# DASH_V_3_POTS.net
KiCad netlist of a schematic drawn in Altium Designer
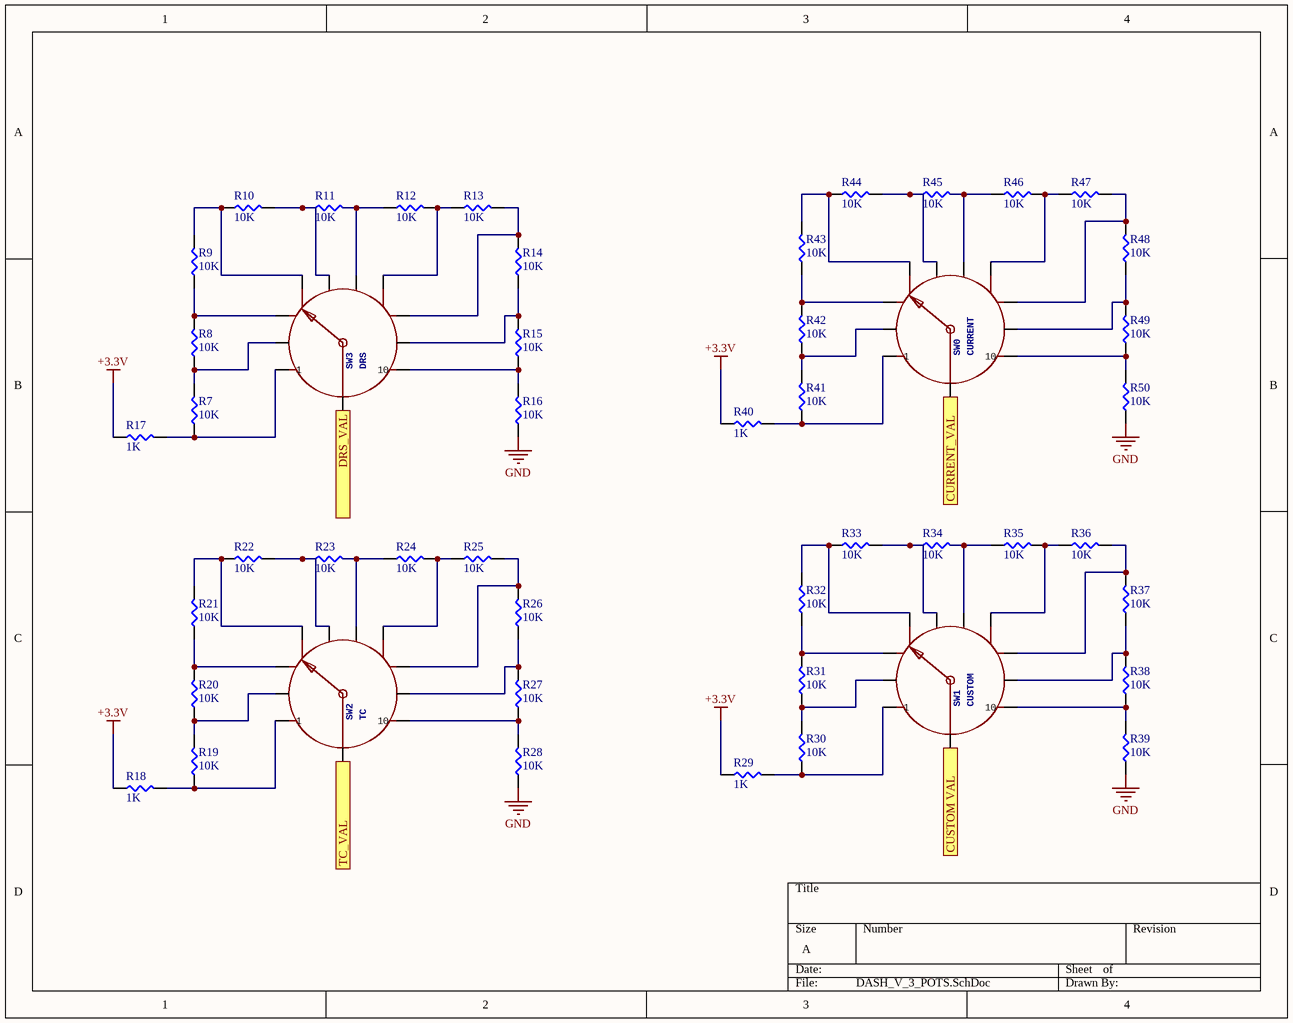
[diagram p0: DASH_V_3_POTS.SchDoc]

(export (version "E")
  (design (tool "Eeschema 10.0.6"))
  (components
    (comp (ref "R7")
      (value "10K")
      (footprint "RES-0603")
      (libsource (lib "ife19_Elec_Library") (part "RES-0603"))
    )
    (comp (ref "R8")
      (value "10K")
      (footprint "RES-0603")
      (libsource (lib "ife19_Elec_Library") (part "RES-0603"))
    )
    (comp (ref "R9")
      (value "10K")
      (footprint "RES-0603")
      (libsource (lib "ife19_Elec_Library") (part "RES-0603"))
    )
    (comp (ref "R10")
      (value "10K")
      (footprint "RES-0603")
      (libsource (lib "ife19_Elec_Library") (part "RES-0603"))
    )
    (comp (ref "R11")
      (value "10K")
      (footprint "RES-0603")
      (libsource (lib "ife19_Elec_Library") (part "RES-0603"))
    )
    (comp (ref "R12")
      (value "10K")
      (footprint "RES-0603")
      (libsource (lib "ife19_Elec_Library") (part "RES-0603"))
    )
    (comp (ref "R13")
      (value "10K")
      (footprint "RES-0603")
      (libsource (lib "ife19_Elec_Library") (part "RES-0603"))
    )
    (comp (ref "R14")
      (value "10K")
      (footprint "RES-0603")
      (libsource (lib "ife19_Elec_Library") (part "RES-0603"))
    )
    (comp (ref "R15")
      (value "10K")
      (footprint "RES-0603")
      (libsource (lib "ife19_Elec_Library") (part "RES-0603"))
    )
    (comp (ref "R16")
      (value "10K")
      (footprint "RES-0603")
      (libsource (lib "ife19_Elec_Library") (part "RES-0603"))
    )
    (comp (ref "R17")
      (value "1K")
      (footprint "RES-0603")
      (libsource (lib "ife19_Elec_Library") (part "RES-0603"))
    )
    (comp (ref "R18")
      (value "1K")
      (footprint "RES-0603")
      (libsource (lib "ife19_Elec_Library") (part "RES-0603"))
    )
    (comp (ref "R19")
      (value "10K")
      (footprint "RES-0603")
      (libsource (lib "ife19_Elec_Library") (part "RES-0603"))
    )
    (comp (ref "R20")
      (value "10K")
      (footprint "RES-0603")
      (libsource (lib "ife19_Elec_Library") (part "RES-0603"))
    )
    (comp (ref "R21")
      (value "10K")
      (footprint "RES-0603")
      (libsource (lib "ife19_Elec_Library") (part "RES-0603"))
    )
    (comp (ref "R22")
      (value "10K")
      (footprint "RES-0603")
      (libsource (lib "ife19_Elec_Library") (part "RES-0603"))
    )
    (comp (ref "R23")
      (value "10K")
      (footprint "RES-0603")
      (libsource (lib "ife19_Elec_Library") (part "RES-0603"))
    )
    (comp (ref "R24")
      (value "10K")
      (footprint "RES-0603")
      (libsource (lib "ife19_Elec_Library") (part "RES-0603"))
    )
    (comp (ref "R25")
      (value "10K")
      (footprint "RES-0603")
      (libsource (lib "ife19_Elec_Library") (part "RES-0603"))
    )
    (comp (ref "R26")
      (value "10K")
      (footprint "RES-0603")
      (libsource (lib "ife19_Elec_Library") (part "RES-0603"))
    )
    (comp (ref "R27")
      (value "10K")
      (footprint "RES-0603")
      (libsource (lib "ife19_Elec_Library") (part "RES-0603"))
    )
    (comp (ref "R28")
      (value "10K")
      (footprint "RES-0603")
      (libsource (lib "ife19_Elec_Library") (part "RES-0603"))
    )
    (comp (ref "R29")
      (value "1K")
      (footprint "RES-0603")
      (libsource (lib "ife19_Elec_Library") (part "RES-0603"))
    )
    (comp (ref "R30")
      (value "10K")
      (footprint "RES-0603")
      (libsource (lib "ife19_Elec_Library") (part "RES-0603"))
    )
    (comp (ref "R31")
      (value "10K")
      (footprint "RES-0603")
      (libsource (lib "ife19_Elec_Library") (part "RES-0603"))
    )
    (comp (ref "R32")
      (value "10K")
      (footprint "RES-0603")
      (libsource (lib "ife19_Elec_Library") (part "RES-0603"))
    )
    (comp (ref "R33")
      (value "10K")
      (footprint "RES-0603")
      (libsource (lib "ife19_Elec_Library") (part "RES-0603"))
    )
    (comp (ref "R34")
      (value "10K")
      (footprint "RES-0603")
      (libsource (lib "ife19_Elec_Library") (part "RES-0603"))
    )
    (comp (ref "R35")
      (value "10K")
      (footprint "RES-0603")
      (libsource (lib "ife19_Elec_Library") (part "RES-0603"))
    )
    (comp (ref "R36")
      (value "10K")
      (footprint "RES-0603")
      (libsource (lib "ife19_Elec_Library") (part "RES-0603"))
    )
    (comp (ref "R37")
      (value "10K")
      (footprint "RES-0603")
      (libsource (lib "ife19_Elec_Library") (part "RES-0603"))
    )
    (comp (ref "R38")
      (value "10K")
      (footprint "RES-0603")
      (libsource (lib "ife19_Elec_Library") (part "RES-0603"))
    )
    (comp (ref "R39")
      (value "10K")
      (footprint "RES-0603")
      (libsource (lib "ife19_Elec_Library") (part "RES-0603"))
    )
    (comp (ref "R40")
      (value "1K")
      (footprint "RES-0603")
      (libsource (lib "ife19_Elec_Library") (part "RES-0603"))
    )
    (comp (ref "R41")
      (value "10K")
      (footprint "RES-0603")
      (libsource (lib "ife19_Elec_Library") (part "RES-0603"))
    )
    (comp (ref "R42")
      (value "10K")
      (footprint "RES-0603")
      (libsource (lib "ife19_Elec_Library") (part "RES-0603"))
    )
    (comp (ref "R43")
      (value "10K")
      (footprint "RES-0603")
      (libsource (lib "ife19_Elec_Library") (part "RES-0603"))
    )
    (comp (ref "R44")
      (value "10K")
      (footprint "RES-0603")
      (libsource (lib "ife19_Elec_Library") (part "RES-0603"))
    )
    (comp (ref "R45")
      (value "10K")
      (footprint "RES-0603")
      (libsource (lib "ife19_Elec_Library") (part "RES-0603"))
    )
    (comp (ref "R46")
      (value "10K")
      (footprint "RES-0603")
      (libsource (lib "ife19_Elec_Library") (part "RES-0603"))
    )
    (comp (ref "R47")
      (value "10K")
      (footprint "RES-0603")
      (libsource (lib "ife19_Elec_Library") (part "RES-0603"))
    )
    (comp (ref "R48")
      (value "10K")
      (footprint "RES-0603")
      (libsource (lib "ife19_Elec_Library") (part "RES-0603"))
    )
    (comp (ref "R49")
      (value "10K")
      (footprint "RES-0603")
      (libsource (lib "ife19_Elec_Library") (part "RES-0603"))
    )
    (comp (ref "R50")
      (value "10K")
      (footprint "RES-0603")
      (libsource (lib "ife19_Elec_Library") (part "RES-0603"))
    )
    (comp (ref "SW0")
      (value "CURRENT")
      (footprint "SPARKFUN-ELECTROMECHANICAL_ROTARY_SWITCH_1X10_KIT")
      (libsource (lib "Rotary_Switch_Potentiometer_v10") (part "SPARKFUN-ELECTROMECHANICAL_SWITCH_ROTARY_1X10KIT"))
    )
    (comp (ref "SW1")
      (value "CUSTOM")
      (footprint "SPARKFUN-ELECTROMECHANICAL_ROTARY_SWITCH_1X10_KIT")
      (libsource (lib "Rotary_Switch_Potentiometer_v10") (part "SPARKFUN-ELECTROMECHANICAL_SWITCH_ROTARY_1X10KIT"))
    )
    (comp (ref "SW2")
      (value "TC")
      (footprint "SPARKFUN-ELECTROMECHANICAL_ROTARY_SWITCH_1X10_KIT")
      (libsource (lib "Rotary_Switch_Potentiometer_v10") (part "SPARKFUN-ELECTROMECHANICAL_SWITCH_ROTARY_1X10KIT"))
    )
    (comp (ref "SW3")
      (value "DRS")
      (footprint "SPARKFUN-ELECTROMECHANICAL_ROTARY_SWITCH_1X10_KIT")
      (libsource (lib "Rotary_Switch_Potentiometer_v10") (part "SPARKFUN-ELECTROMECHANICAL_SWITCH_ROTARY_1X10KIT"))
    )
  )
  (nets
    (net (code "1") (name "+3.3V") (class "Default")
      (node (ref "R17") (pin "1") (pinfunction "1_1") (pintype "passive"))
      (node (ref "R18") (pin "1") (pinfunction "1_1") (pintype "passive"))
      (node (ref "R29") (pin "1") (pinfunction "1_1") (pintype "passive"))
      (node (ref "R40") (pin "1") (pinfunction "1_1") (pintype "passive"))
    )
    (net (code "2") (name "/CURRENT_VAL") (class "Default")
      (node (ref "SW0") (pin "COMMON") (pinfunction "COMMON_COMMON") (pintype "passive"))
    )
    (net (code "3") (name "/CUSTOM VAL") (class "Default")
      (node (ref "SW1") (pin "COMMON") (pinfunction "COMMON_COMMON") (pintype "passive"))
    )
    (net (code "4") (name "/DRS_VAL") (class "Default")
      (node (ref "SW3") (pin "COMMON") (pinfunction "COMMON_COMMON") (pintype "passive"))
    )
    (net (code "5") (name "/TC_VAL") (class "Default")
      (node (ref "SW2") (pin "COMMON") (pinfunction "COMMON_COMMON") (pintype "passive"))
    )
    (net (code "6") (name "GND") (class "Default")
      (node (ref "R16") (pin "1") (pinfunction "1_1") (pintype "passive"))
      (node (ref "R28") (pin "1") (pinfunction "1_1") (pintype "passive"))
      (node (ref "R39") (pin "1") (pinfunction "1_1") (pintype "passive"))
      (node (ref "R50") (pin "1") (pinfunction "1_1") (pintype "passive"))
    )
    (net (code "7") (name "Net-(R7-Pad2)") (class "Default")
      (node (ref "R7") (pin "2") (pinfunction "2_2") (pintype "passive"))
      (node (ref "R8") (pin "1") (pinfunction "1_1") (pintype "passive"))
      (node (ref "SW3") (pin "2") (pinfunction "2_2") (pintype "passive"))
    )
    (net (code "8") (name "Net-(R8-Pad2)") (class "Default")
      (node (ref "R8") (pin "2") (pinfunction "2_2") (pintype "passive"))
      (node (ref "R9") (pin "1") (pinfunction "1_1") (pintype "passive"))
      (node (ref "SW3") (pin "3") (pinfunction "3_3") (pintype "passive"))
    )
    (net (code "9") (name "Net-(R10-Pad1)") (class "Default")
      (node (ref "R10") (pin "1") (pinfunction "1_1") (pintype "passive"))
      (node (ref "R9") (pin "2") (pinfunction "2_2") (pintype "passive"))
      (node (ref "SW3") (pin "4") (pinfunction "4_4") (pintype "passive"))
    )
    (net (code "10") (name "Net-(R10-Pad2)") (class "Default")
      (node (ref "R10") (pin "2") (pinfunction "2_2") (pintype "passive"))
      (node (ref "R11") (pin "1") (pinfunction "1_1") (pintype "passive"))
      (node (ref "SW3") (pin "5") (pinfunction "5_5") (pintype "passive"))
    )
    (net (code "11") (name "Net-(R11-Pad2)") (class "Default")
      (node (ref "R11") (pin "2") (pinfunction "2_2") (pintype "passive"))
      (node (ref "R12") (pin "1") (pinfunction "1_1") (pintype "passive"))
      (node (ref "SW3") (pin "6") (pinfunction "6_6") (pintype "passive"))
    )
    (net (code "12") (name "Net-(R12-Pad2)") (class "Default")
      (node (ref "R12") (pin "2") (pinfunction "2_2") (pintype "passive"))
      (node (ref "R13") (pin "1") (pinfunction "1_1") (pintype "passive"))
      (node (ref "SW3") (pin "7") (pinfunction "7_7") (pintype "passive"))
    )
    (net (code "13") (name "Net-(R13-Pad2)") (class "Default")
      (node (ref "R13") (pin "2") (pinfunction "2_2") (pintype "passive"))
      (node (ref "R14") (pin "2") (pinfunction "2_2") (pintype "passive"))
      (node (ref "SW3") (pin "8") (pinfunction "8_8") (pintype "passive"))
    )
    (net (code "14") (name "Net-(R14-Pad1)") (class "Default")
      (node (ref "R14") (pin "1") (pinfunction "1_1") (pintype "passive"))
      (node (ref "R15") (pin "2") (pinfunction "2_2") (pintype "passive"))
      (node (ref "SW3") (pin "9") (pinfunction "9_9") (pintype "passive"))
    )
    (net (code "15") (name "Net-(R15-Pad1)") (class "Default")
      (node (ref "R15") (pin "1") (pinfunction "1_1") (pintype "passive"))
      (node (ref "R16") (pin "2") (pinfunction "2_2") (pintype "passive"))
      (node (ref "SW3") (pin "10") (pinfunction "10_10") (pintype "passive"))
    )
    (net (code "16") (name "Net-(R17-Pad2)") (class "Default")
      (node (ref "R17") (pin "2") (pinfunction "2_2") (pintype "passive"))
      (node (ref "R7") (pin "1") (pinfunction "1_1") (pintype "passive"))
      (node (ref "SW3") (pin "1") (pinfunction "1_1") (pintype "passive"))
    )
    (net (code "17") (name "Net-(R18-Pad2)") (class "Default")
      (node (ref "R18") (pin "2") (pinfunction "2_2") (pintype "passive"))
      (node (ref "R19") (pin "1") (pinfunction "1_1") (pintype "passive"))
      (node (ref "SW2") (pin "1") (pinfunction "1_1") (pintype "passive"))
    )
    (net (code "18") (name "Net-(R19-Pad2)") (class "Default")
      (node (ref "R19") (pin "2") (pinfunction "2_2") (pintype "passive"))
      (node (ref "R20") (pin "1") (pinfunction "1_1") (pintype "passive"))
      (node (ref "SW2") (pin "2") (pinfunction "2_2") (pintype "passive"))
    )
    (net (code "19") (name "Net-(R20-Pad2)") (class "Default")
      (node (ref "R20") (pin "2") (pinfunction "2_2") (pintype "passive"))
      (node (ref "R21") (pin "1") (pinfunction "1_1") (pintype "passive"))
      (node (ref "SW2") (pin "3") (pinfunction "3_3") (pintype "passive"))
    )
    (net (code "20") (name "Net-(R21-Pad2)") (class "Default")
      (node (ref "R21") (pin "2") (pinfunction "2_2") (pintype "passive"))
      (node (ref "R22") (pin "1") (pinfunction "1_1") (pintype "passive"))
      (node (ref "SW2") (pin "4") (pinfunction "4_4") (pintype "passive"))
    )
    (net (code "21") (name "Net-(R22-Pad2)") (class "Default")
      (node (ref "R22") (pin "2") (pinfunction "2_2") (pintype "passive"))
      (node (ref "R23") (pin "1") (pinfunction "1_1") (pintype "passive"))
      (node (ref "SW2") (pin "5") (pinfunction "5_5") (pintype "passive"))
    )
    (net (code "22") (name "Net-(R23-Pad2)") (class "Default")
      (node (ref "R23") (pin "2") (pinfunction "2_2") (pintype "passive"))
      (node (ref "R24") (pin "1") (pinfunction "1_1") (pintype "passive"))
      (node (ref "SW2") (pin "6") (pinfunction "6_6") (pintype "passive"))
    )
    (net (code "23") (name "Net-(R24-Pad2)") (class "Default")
      (node (ref "R24") (pin "2") (pinfunction "2_2") (pintype "passive"))
      (node (ref "R25") (pin "1") (pinfunction "1_1") (pintype "passive"))
      (node (ref "SW2") (pin "7") (pinfunction "7_7") (pintype "passive"))
    )
    (net (code "24") (name "Net-(R25-Pad2)") (class "Default")
      (node (ref "R25") (pin "2") (pinfunction "2_2") (pintype "passive"))
      (node (ref "R26") (pin "2") (pinfunction "2_2") (pintype "passive"))
      (node (ref "SW2") (pin "8") (pinfunction "8_8") (pintype "passive"))
    )
    (net (code "25") (name "Net-(R26-Pad1)") (class "Default")
      (node (ref "R26") (pin "1") (pinfunction "1_1") (pintype "passive"))
      (node (ref "R27") (pin "2") (pinfunction "2_2") (pintype "passive"))
      (node (ref "SW2") (pin "9") (pinfunction "9_9") (pintype "passive"))
    )
    (net (code "26") (name "Net-(R27-Pad1)") (class "Default")
      (node (ref "R27") (pin "1") (pinfunction "1_1") (pintype "passive"))
      (node (ref "R28") (pin "2") (pinfunction "2_2") (pintype "passive"))
      (node (ref "SW2") (pin "10") (pinfunction "10_10") (pintype "passive"))
    )
    (net (code "27") (name "Net-(R29-Pad2)") (class "Default")
      (node (ref "R29") (pin "2") (pinfunction "2_2") (pintype "passive"))
      (node (ref "R30") (pin "1") (pinfunction "1_1") (pintype "passive"))
      (node (ref "SW1") (pin "1") (pinfunction "1_1") (pintype "passive"))
    )
    (net (code "28") (name "Net-(R30-Pad2)") (class "Default")
      (node (ref "R30") (pin "2") (pinfunction "2_2") (pintype "passive"))
      (node (ref "R31") (pin "1") (pinfunction "1_1") (pintype "passive"))
      (node (ref "SW1") (pin "2") (pinfunction "2_2") (pintype "passive"))
    )
    (net (code "29") (name "Net-(R31-Pad2)") (class "Default")
      (node (ref "R31") (pin "2") (pinfunction "2_2") (pintype "passive"))
      (node (ref "R32") (pin "1") (pinfunction "1_1") (pintype "passive"))
      (node (ref "SW1") (pin "3") (pinfunction "3_3") (pintype "passive"))
    )
    (net (code "30") (name "Net-(R32-Pad2)") (class "Default")
      (node (ref "R32") (pin "2") (pinfunction "2_2") (pintype "passive"))
      (node (ref "R33") (pin "1") (pinfunction "1_1") (pintype "passive"))
      (node (ref "SW1") (pin "4") (pinfunction "4_4") (pintype "passive"))
    )
    (net (code "31") (name "Net-(R33-Pad2)") (class "Default")
      (node (ref "R33") (pin "2") (pinfunction "2_2") (pintype "passive"))
      (node (ref "R34") (pin "1") (pinfunction "1_1") (pintype "passive"))
      (node (ref "SW1") (pin "5") (pinfunction "5_5") (pintype "passive"))
    )
    (net (code "32") (name "Net-(R34-Pad2)") (class "Default")
      (node (ref "R34") (pin "2") (pinfunction "2_2") (pintype "passive"))
      (node (ref "R35") (pin "1") (pinfunction "1_1") (pintype "passive"))
      (node (ref "SW1") (pin "6") (pinfunction "6_6") (pintype "passive"))
    )
    (net (code "33") (name "Net-(R35-Pad2)") (class "Default")
      (node (ref "R35") (pin "2") (pinfunction "2_2") (pintype "passive"))
      (node (ref "R36") (pin "1") (pinfunction "1_1") (pintype "passive"))
      (node (ref "SW1") (pin "7") (pinfunction "7_7") (pintype "passive"))
    )
    (net (code "34") (name "Net-(R36-Pad2)") (class "Default")
      (node (ref "R36") (pin "2") (pinfunction "2_2") (pintype "passive"))
      (node (ref "R37") (pin "2") (pinfunction "2_2") (pintype "passive"))
      (node (ref "SW1") (pin "8") (pinfunction "8_8") (pintype "passive"))
    )
    (net (code "35") (name "Net-(R37-Pad1)") (class "Default")
      (node (ref "R37") (pin "1") (pinfunction "1_1") (pintype "passive"))
      (node (ref "R38") (pin "2") (pinfunction "2_2") (pintype "passive"))
      (node (ref "SW1") (pin "9") (pinfunction "9_9") (pintype "passive"))
    )
    (net (code "36") (name "Net-(R38-Pad1)") (class "Default")
      (node (ref "R38") (pin "1") (pinfunction "1_1") (pintype "passive"))
      (node (ref "R39") (pin "2") (pinfunction "2_2") (pintype "passive"))
      (node (ref "SW1") (pin "10") (pinfunction "10_10") (pintype "passive"))
    )
    (net (code "37") (name "Net-(R40-Pad2)") (class "Default")
      (node (ref "R40") (pin "2") (pinfunction "2_2") (pintype "passive"))
      (node (ref "R41") (pin "1") (pinfunction "1_1") (pintype "passive"))
      (node (ref "SW0") (pin "1") (pinfunction "1_1") (pintype "passive"))
    )
    (net (code "38") (name "Net-(R41-Pad2)") (class "Default")
      (node (ref "R41") (pin "2") (pinfunction "2_2") (pintype "passive"))
      (node (ref "R42") (pin "1") (pinfunction "1_1") (pintype "passive"))
      (node (ref "SW0") (pin "2") (pinfunction "2_2") (pintype "passive"))
    )
    (net (code "39") (name "Net-(R42-Pad2)") (class "Default")
      (node (ref "R42") (pin "2") (pinfunction "2_2") (pintype "passive"))
      (node (ref "R43") (pin "1") (pinfunction "1_1") (pintype "passive"))
      (node (ref "SW0") (pin "3") (pinfunction "3_3") (pintype "passive"))
    )
    (net (code "40") (name "Net-(R43-Pad2)") (class "Default")
      (node (ref "R43") (pin "2") (pinfunction "2_2") (pintype "passive"))
      (node (ref "R44") (pin "1") (pinfunction "1_1") (pintype "passive"))
      (node (ref "SW0") (pin "4") (pinfunction "4_4") (pintype "passive"))
    )
    (net (code "41") (name "Net-(R44-Pad2)") (class "Default")
      (node (ref "R44") (pin "2") (pinfunction "2_2") (pintype "passive"))
      (node (ref "R45") (pin "1") (pinfunction "1_1") (pintype "passive"))
      (node (ref "SW0") (pin "5") (pinfunction "5_5") (pintype "passive"))
    )
    (net (code "42") (name "Net-(R45-Pad2)") (class "Default")
      (node (ref "R45") (pin "2") (pinfunction "2_2") (pintype "passive"))
      (node (ref "R46") (pin "1") (pinfunction "1_1") (pintype "passive"))
      (node (ref "SW0") (pin "6") (pinfunction "6_6") (pintype "passive"))
    )
    (net (code "43") (name "Net-(R46-Pad2)") (class "Default")
      (node (ref "R46") (pin "2") (pinfunction "2_2") (pintype "passive"))
      (node (ref "R47") (pin "1") (pinfunction "1_1") (pintype "passive"))
      (node (ref "SW0") (pin "7") (pinfunction "7_7") (pintype "passive"))
    )
    (net (code "44") (name "Net-(R47-Pad2)") (class "Default")
      (node (ref "R47") (pin "2") (pinfunction "2_2") (pintype "passive"))
      (node (ref "R48") (pin "2") (pinfunction "2_2") (pintype "passive"))
      (node (ref "SW0") (pin "8") (pinfunction "8_8") (pintype "passive"))
    )
    (net (code "45") (name "Net-(R48-Pad1)") (class "Default")
      (node (ref "R48") (pin "1") (pinfunction "1_1") (pintype "passive"))
      (node (ref "R49") (pin "2") (pinfunction "2_2") (pintype "passive"))
      (node (ref "SW0") (pin "9") (pinfunction "9_9") (pintype "passive"))
    )
    (net (code "46") (name "Net-(R49-Pad1)") (class "Default")
      (node (ref "R49") (pin "1") (pinfunction "1_1") (pintype "passive"))
      (node (ref "R50") (pin "2") (pinfunction "2_2") (pintype "passive"))
      (node (ref "SW0") (pin "10") (pinfunction "10_10") (pintype "passive"))
    )
  )
)
